# 04_ARM_B.net
KiCad netlist of a schematic drawn in Altium Designer
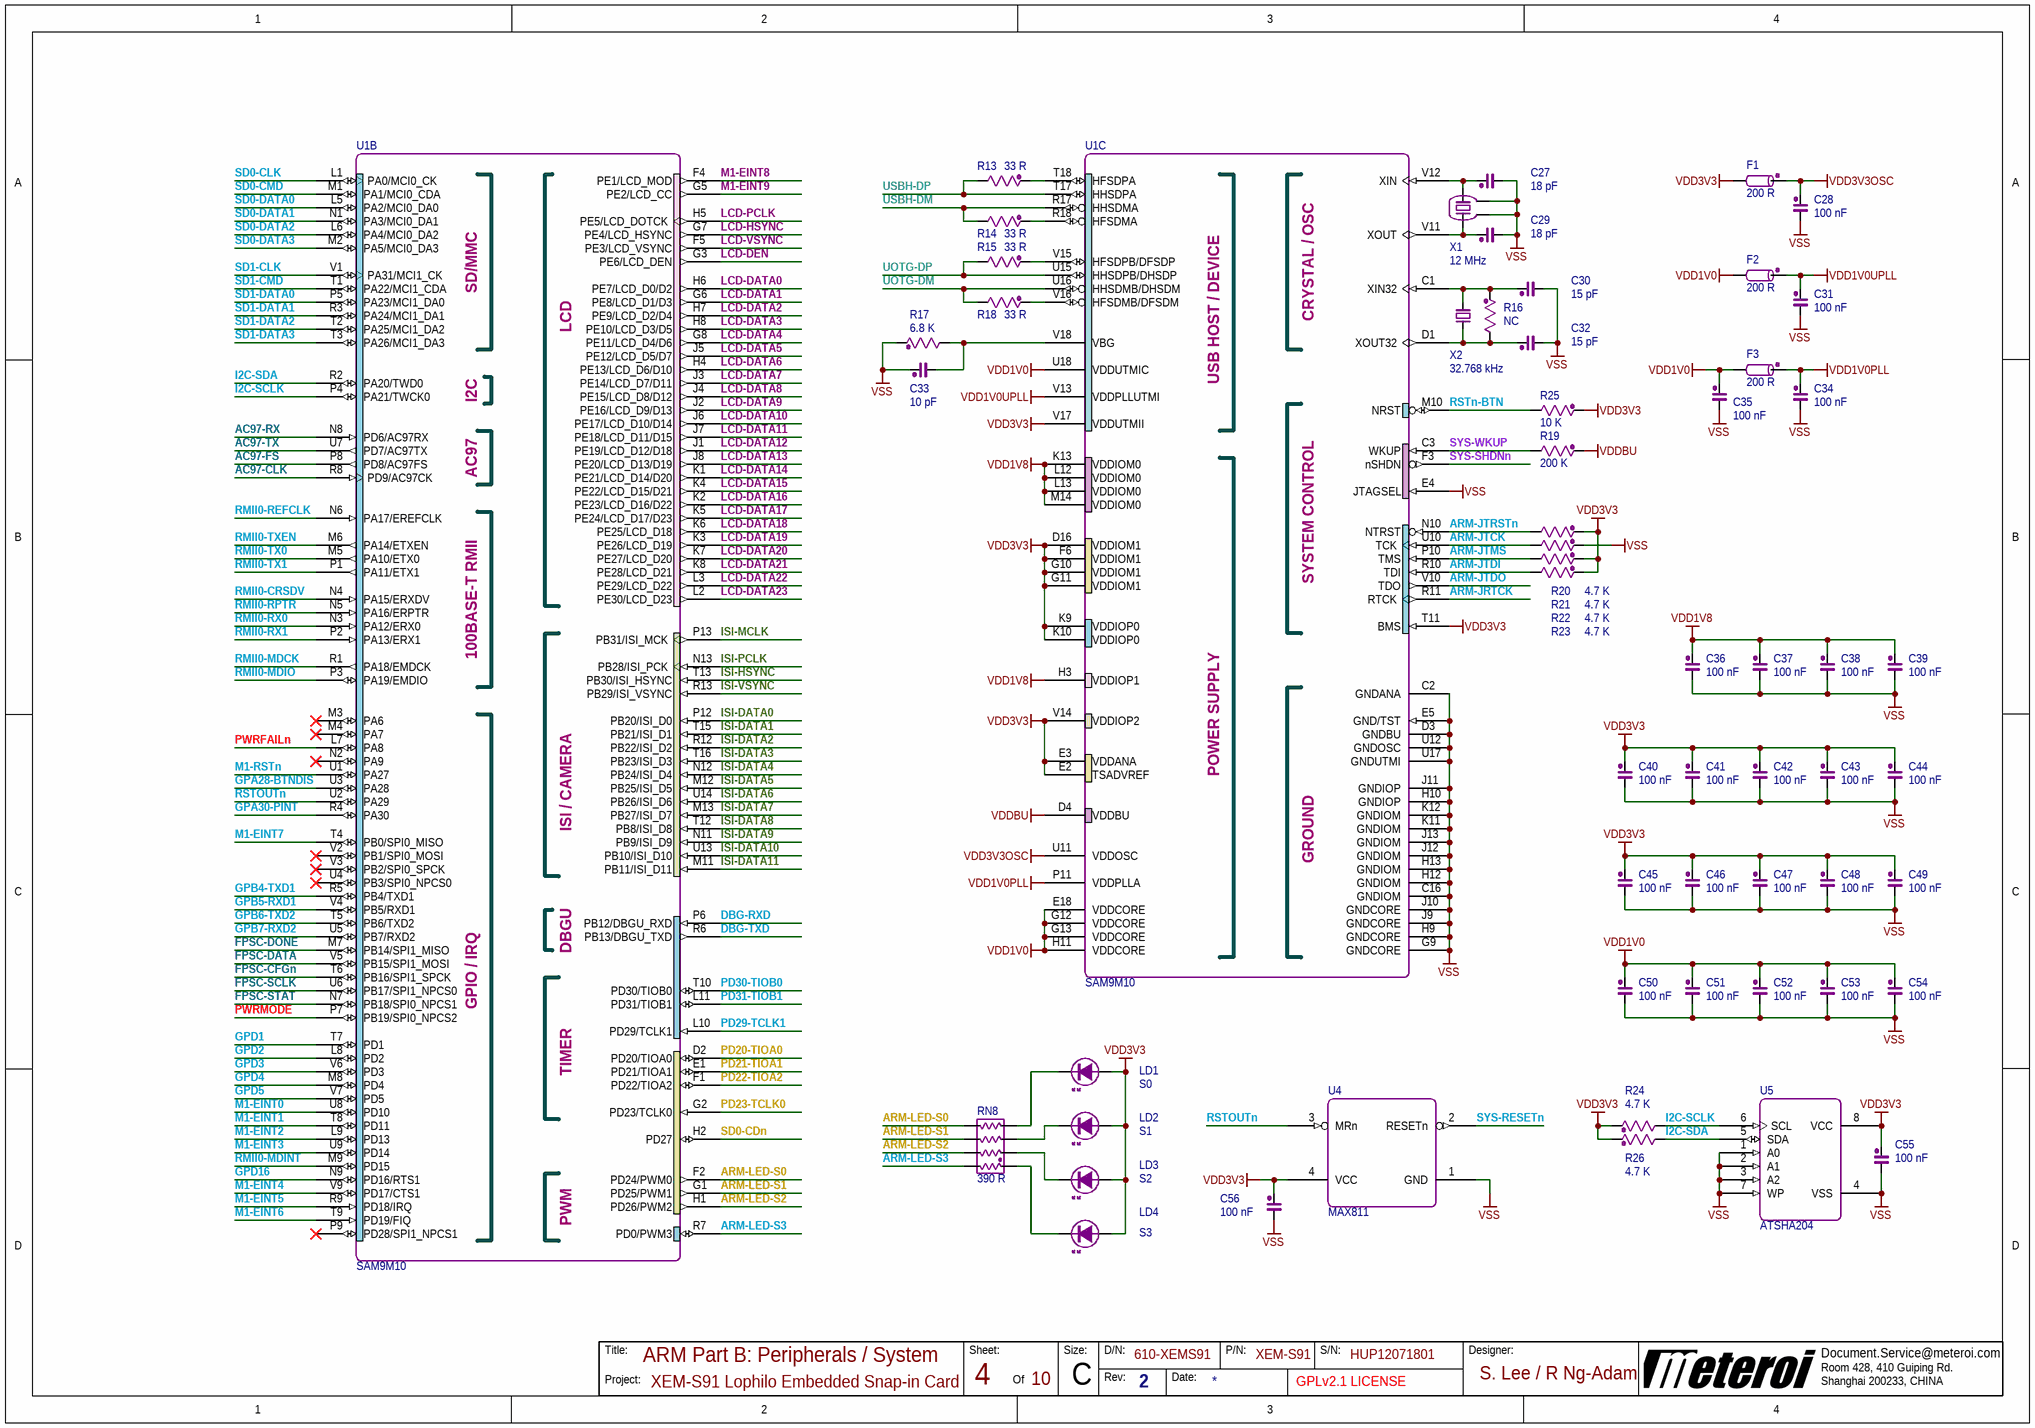
[diagram p0: 04_ARM_B.SchDoc]

(export (version "E")
  (design (tool "Eeschema 10.0.6"))
  (components
    (comp (ref "C27")
      (value "18 pF")
      (footprint "0402A1")
      (description "Normal Capacitor")
      (fields
        (field (name "PARTNUMBER") "0")
        (field (name "PUBLISHER") "Cowin")
        (field (name "DESIGNER") "shyul")
      )
      (libsource (lib "Basc_1_Passive") (part "CAP"))
    )
    (comp (ref "C28")
      (value "100 nF")
      (footprint "0402A1")
      (description "Normal Capacitor")
      (fields
        (field (name "PARTNUMBER") "0")
        (field (name "PUBLISHER") "Cowin")
        (field (name "DESIGNER") "shyul")
      )
      (libsource (lib "") (part "CAP_1"))
    )
    (comp (ref "C29")
      (value "18 pF")
      (footprint "0402A1")
      (description "Normal Capacitor")
      (fields
        (field (name "PARTNUMBER") "0")
        (field (name "PUBLISHER") "Cowin")
        (field (name "DESIGNER") "shyul")
      )
      (libsource (lib "Basc_1_Passive") (part "CAP"))
    )
    (comp (ref "C30")
      (value "15 pF")
      (footprint "0402A1")
      (description "Normal Capacitor")
      (fields
        (field (name "PARTNUMBER") "0")
        (field (name "PUBLISHER") "Cowin")
        (field (name "DESIGNER") "shyul")
      )
      (libsource (lib "Basc_1_Passive") (part "CAP"))
    )
    (comp (ref "C31")
      (value "100 nF")
      (footprint "0402A1")
      (description "Normal Capacitor")
      (fields
        (field (name "PARTNUMBER") "0")
        (field (name "PUBLISHER") "Cowin")
        (field (name "DESIGNER") "shyul")
      )
      (libsource (lib "") (part "CAP_1"))
    )
    (comp (ref "C32")
      (value "15 pF")
      (footprint "0402A1")
      (description "Normal Capacitor")
      (fields
        (field (name "PARTNUMBER") "0")
        (field (name "PUBLISHER") "Cowin")
        (field (name "DESIGNER") "shyul")
      )
      (libsource (lib "Basc_1_Passive") (part "CAP"))
    )
    (comp (ref "C33")
      (value "10 pF")
      (footprint "0402A1")
      (description "Normal Capacitor")
      (fields
        (field (name "PARTNUMBER") "0")
        (field (name "PUBLISHER") "Cowin")
        (field (name "DESIGNER") "shyul")
      )
      (libsource (lib "Basc_1_Passive") (part "CAP"))
    )
    (comp (ref "C34")
      (value "100 nF")
      (footprint "0402A1")
      (description "Normal Capacitor")
      (fields
        (field (name "PARTNUMBER") "0")
        (field (name "PUBLISHER") "Cowin")
        (field (name "DESIGNER") "shyul")
      )
      (libsource (lib "") (part "CAP_1"))
    )
    (comp (ref "C35")
      (value "100 nF")
      (footprint "0402A1")
      (description "Normal Capacitor")
      (fields
        (field (name "PARTNUMBER") "0")
        (field (name "PUBLISHER") "Cowin")
        (field (name "DESIGNER") "shyul")
      )
      (libsource (lib "") (part "CAP_1"))
    )
    (comp (ref "C36")
      (value "100 nF")
      (footprint "0402A1")
      (description "Normal Capacitor")
      (fields
        (field (name "PARTNUMBER") "0")
        (field (name "PUBLISHER") "Cowin")
        (field (name "DESIGNER") "shyul")
      )
      (libsource (lib "") (part "CAP_1"))
    )
    (comp (ref "C37")
      (value "100 nF")
      (footprint "0402A1")
      (description "Normal Capacitor")
      (fields
        (field (name "PARTNUMBER") "0")
        (field (name "PUBLISHER") "Cowin")
        (field (name "DESIGNER") "shyul")
      )
      (libsource (lib "") (part "CAP_1"))
    )
    (comp (ref "C38")
      (value "100 nF")
      (footprint "0402A1")
      (description "Normal Capacitor")
      (fields
        (field (name "PARTNUMBER") "0")
        (field (name "PUBLISHER") "Cowin")
        (field (name "DESIGNER") "shyul")
      )
      (libsource (lib "") (part "CAP_1"))
    )
    (comp (ref "C39")
      (value "100 nF")
      (footprint "0402A1")
      (description "Normal Capacitor")
      (fields
        (field (name "PARTNUMBER") "0")
        (field (name "PUBLISHER") "Cowin")
        (field (name "DESIGNER") "shyul")
      )
      (libsource (lib "") (part "CAP_1"))
    )
    (comp (ref "C40")
      (value "100 nF")
      (footprint "0402A1")
      (description "Normal Capacitor")
      (fields
        (field (name "PARTNUMBER") "0")
        (field (name "PUBLISHER") "Cowin")
        (field (name "DESIGNER") "shyul")
      )
      (libsource (lib "") (part "CAP_1"))
    )
    (comp (ref "C41")
      (value "100 nF")
      (footprint "0402A1")
      (description "Normal Capacitor")
      (fields
        (field (name "PARTNUMBER") "0")
        (field (name "PUBLISHER") "Cowin")
        (field (name "DESIGNER") "shyul")
      )
      (libsource (lib "") (part "CAP_1"))
    )
    (comp (ref "C42")
      (value "100 nF")
      (footprint "0402A1")
      (description "Normal Capacitor")
      (fields
        (field (name "PARTNUMBER") "0")
        (field (name "PUBLISHER") "Cowin")
        (field (name "DESIGNER") "shyul")
      )
      (libsource (lib "") (part "CAP_1"))
    )
    (comp (ref "C43")
      (value "100 nF")
      (footprint "0402A1")
      (description "Normal Capacitor")
      (fields
        (field (name "PARTNUMBER") "0")
        (field (name "PUBLISHER") "Cowin")
        (field (name "DESIGNER") "shyul")
      )
      (libsource (lib "") (part "CAP_1"))
    )
    (comp (ref "C44")
      (value "100 nF")
      (footprint "0402A1")
      (description "Normal Capacitor")
      (fields
        (field (name "PARTNUMBER") "0")
        (field (name "PUBLISHER") "Cowin")
        (field (name "DESIGNER") "shyul")
      )
      (libsource (lib "") (part "CAP_1"))
    )
    (comp (ref "C45")
      (value "100 nF")
      (footprint "0402A1")
      (description "Normal Capacitor")
      (fields
        (field (name "PARTNUMBER") "0")
        (field (name "PUBLISHER") "Cowin")
        (field (name "DESIGNER") "shyul")
      )
      (libsource (lib "") (part "CAP_1"))
    )
    (comp (ref "C46")
      (value "100 nF")
      (footprint "0402A1")
      (description "Normal Capacitor")
      (fields
        (field (name "PARTNUMBER") "0")
        (field (name "PUBLISHER") "Cowin")
        (field (name "DESIGNER") "shyul")
      )
      (libsource (lib "") (part "CAP_1"))
    )
    (comp (ref "C47")
      (value "100 nF")
      (footprint "0402A1")
      (description "Normal Capacitor")
      (fields
        (field (name "PARTNUMBER") "0")
        (field (name "PUBLISHER") "Cowin")
        (field (name "DESIGNER") "shyul")
      )
      (libsource (lib "") (part "CAP_1"))
    )
    (comp (ref "C48")
      (value "100 nF")
      (footprint "0402A1")
      (description "Normal Capacitor")
      (fields
        (field (name "PARTNUMBER") "0")
        (field (name "PUBLISHER") "Cowin")
        (field (name "DESIGNER") "shyul")
      )
      (libsource (lib "") (part "CAP_1"))
    )
    (comp (ref "C49")
      (value "100 nF")
      (footprint "0402A1")
      (description "Normal Capacitor")
      (fields
        (field (name "PARTNUMBER") "0")
        (field (name "PUBLISHER") "Cowin")
        (field (name "DESIGNER") "shyul")
      )
      (libsource (lib "") (part "CAP_1"))
    )
    (comp (ref "C50")
      (value "100 nF")
      (footprint "0402A1")
      (description "Normal Capacitor")
      (fields
        (field (name "PARTNUMBER") "0")
        (field (name "PUBLISHER") "Cowin")
        (field (name "DESIGNER") "shyul")
      )
      (libsource (lib "") (part "CAP_1"))
    )
    (comp (ref "C51")
      (value "100 nF")
      (footprint "0402A1")
      (description "Normal Capacitor")
      (fields
        (field (name "PARTNUMBER") "0")
        (field (name "PUBLISHER") "Cowin")
        (field (name "DESIGNER") "shyul")
      )
      (libsource (lib "") (part "CAP_1"))
    )
    (comp (ref "C52")
      (value "100 nF")
      (footprint "0402A1")
      (description "Normal Capacitor")
      (fields
        (field (name "PARTNUMBER") "0")
        (field (name "PUBLISHER") "Cowin")
        (field (name "DESIGNER") "shyul")
      )
      (libsource (lib "") (part "CAP_1"))
    )
    (comp (ref "C53")
      (value "100 nF")
      (footprint "0402A1")
      (description "Normal Capacitor")
      (fields
        (field (name "PARTNUMBER") "0")
        (field (name "PUBLISHER") "Cowin")
        (field (name "DESIGNER") "shyul")
      )
      (libsource (lib "") (part "CAP_1"))
    )
    (comp (ref "C54")
      (value "100 nF")
      (footprint "0402A1")
      (description "Normal Capacitor")
      (fields
        (field (name "PARTNUMBER") "0")
        (field (name "PUBLISHER") "Cowin")
        (field (name "DESIGNER") "shyul")
      )
      (libsource (lib "") (part "CAP_1"))
    )
    (comp (ref "C55")
      (value "100 nF")
      (footprint "0402A1")
      (description "Normal Capacitor")
      (fields
        (field (name "PARTNUMBER") "0")
        (field (name "PUBLISHER") "Cowin")
        (field (name "DESIGNER") "shyul")
      )
      (libsource (lib "") (part "CAP_1"))
    )
    (comp (ref "C56")
      (value "100 nF")
      (footprint "0402A1")
      (description "Normal Capacitor")
      (fields
        (field (name "PARTNUMBER") "0")
        (field (name "PUBLISHER") "Cowin")
        (field (name "DESIGNER") "shyul")
      )
      (libsource (lib "") (part "CAP_1"))
    )
    (comp (ref "F1")
      (value "200 R")
      (footprint "0402A3")
      (description "EMI Bead")
      (fields
        (field (name "PARTNUMBER") "BLM")
        (field (name "DESIGNER") "shyul")
        (field (name "PUBLISHER") "Cowin")
      )
      (libsource (lib "Basc_2_EMI_Protection") (part "BEAD"))
    )
    (comp (ref "F2")
      (value "200 R")
      (footprint "0402A3")
      (description "EMI Bead")
      (fields
        (field (name "PARTNUMBER") "BLM")
        (field (name "DESIGNER") "shyul")
        (field (name "PUBLISHER") "Cowin")
      )
      (libsource (lib "Basc_2_EMI_Protection") (part "BEAD"))
    )
    (comp (ref "F3")
      (value "200 R")
      (footprint "0402A3")
      (description "EMI Bead")
      (fields
        (field (name "PARTNUMBER") "BLM")
        (field (name "DESIGNER") "shyul")
        (field (name "PUBLISHER") "Cowin")
      )
      (libsource (lib "Basc_2_EMI_Protection") (part "BEAD"))
    )
    (comp (ref "LD1")
      (value "S0")
      (footprint "0603LD")
      (description "LED Single")
      (fields
        (field (name "PARTNUMBER") "0")
        (field (name "DESIGNER") "shyul")
        (field (name "PUBLISHER") "Cowin")
      )
      (libsource (lib "Basc_4_Other") (part "LED"))
    )
    (comp (ref "LD2")
      (value "S1")
      (footprint "0603LD")
      (description "LED Single")
      (fields
        (field (name "PARTNUMBER") "0")
        (field (name "DESIGNER") "shyul")
        (field (name "PUBLISHER") "Cowin")
      )
      (libsource (lib "Basc_4_Other") (part "LED"))
    )
    (comp (ref "LD3")
      (value "S2")
      (footprint "0603LD")
      (description "LED Single")
      (fields
        (field (name "PARTNUMBER") "0")
        (field (name "DESIGNER") "shyul")
        (field (name "PUBLISHER") "Cowin")
      )
      (libsource (lib "Basc_4_Other") (part "LED"))
    )
    (comp (ref "LD4")
      (value "S3")
      (footprint "0603LD")
      (description "LED Single")
      (fields
        (field (name "PARTNUMBER") "0")
        (field (name "DESIGNER") "shyul")
        (field (name "PUBLISHER") "Cowin")
      )
      (libsource (lib "Basc_4_Other") (part "LED"))
    )
    (comp (ref "R13")
      (value "33 R")
      (footprint "0402A2")
      (description "Normal Resistor")
      (fields
        (field (name "PARTNUMBER") "0")
        (field (name "DESIGNER") "shyul")
        (field (name "PUBLISHER") "Cowin")
      )
      (libsource (lib "Basc_1_Passive") (part "RES"))
    )
    (comp (ref "R14")
      (value "33 R")
      (footprint "0402A2")
      (description "Normal Resistor")
      (fields
        (field (name "PARTNUMBER") "0")
        (field (name "DESIGNER") "shyul")
        (field (name "PUBLISHER") "Cowin")
      )
      (libsource (lib "Basc_1_Passive") (part "RES"))
    )
    (comp (ref "R15")
      (value "33 R")
      (footprint "0402A2")
      (description "Normal Resistor")
      (fields
        (field (name "PARTNUMBER") "0")
        (field (name "DESIGNER") "shyul")
        (field (name "PUBLISHER") "Cowin")
      )
      (libsource (lib "Basc_1_Passive") (part "RES"))
    )
    (comp (ref "R16")
      (value "NC")
      (footprint "0402A2")
      (description "Normal Resistor")
      (fields
        (field (name "PARTNUMBER") "0")
        (field (name "DESIGNER") "shyul")
        (field (name "PUBLISHER") "Cowin")
      )
      (libsource (lib "Basc_1_Passive") (part "RES"))
    )
    (comp (ref "R17")
      (value "6.8 K")
      (footprint "0402A2")
      (description "Normal Resistor")
      (fields
        (field (name "PARTNUMBER") "0")
        (field (name "DESIGNER") "shyul")
        (field (name "PUBLISHER") "Cowin")
      )
      (libsource (lib "Basc_1_Passive") (part "RES"))
    )
    (comp (ref "R18")
      (value "33 R")
      (footprint "0402A2")
      (description "Normal Resistor")
      (fields
        (field (name "PARTNUMBER") "0")
        (field (name "DESIGNER") "shyul")
        (field (name "PUBLISHER") "Cowin")
      )
      (libsource (lib "Basc_1_Passive") (part "RES"))
    )
    (comp (ref "R19")
      (value "200 K")
      (footprint "0402A2")
      (description "Normal Resistor")
      (fields
        (field (name "PARTNUMBER") "0")
        (field (name "DESIGNER") "shyul")
        (field (name "PUBLISHER") "Cowin")
      )
      (libsource (lib "Basc_1_Passive") (part "RES"))
    )
    (comp (ref "R20")
      (value "4.7 K")
      (footprint "0402A2")
      (description "Normal Resistor")
      (fields
        (field (name "PARTNUMBER") "0")
        (field (name "DESIGNER") "shyul")
        (field (name "PUBLISHER") "Cowin")
      )
      (libsource (lib "Basc_1_Passive") (part "RES"))
    )
    (comp (ref "R21")
      (value "4.7 K")
      (footprint "0402A2")
      (description "Normal Resistor")
      (fields
        (field (name "PARTNUMBER") "0")
        (field (name "DESIGNER") "shyul")
        (field (name "PUBLISHER") "Cowin")
      )
      (libsource (lib "Basc_1_Passive") (part "RES"))
    )
    (comp (ref "R22")
      (value "4.7 K")
      (footprint "0402A2")
      (description "Normal Resistor")
      (fields
        (field (name "PARTNUMBER") "0")
        (field (name "DESIGNER") "shyul")
        (field (name "PUBLISHER") "Cowin")
      )
      (libsource (lib "Basc_1_Passive") (part "RES"))
    )
    (comp (ref "R23")
      (value "4.7 K")
      (footprint "0402A2")
      (description "Normal Resistor")
      (fields
        (field (name "PARTNUMBER") "0")
        (field (name "DESIGNER") "shyul")
        (field (name "PUBLISHER") "Cowin")
      )
      (libsource (lib "Basc_1_Passive") (part "RES"))
    )
    (comp (ref "R24")
      (value "4.7 K")
      (footprint "0402A2")
      (description "Normal Resistor")
      (fields
        (field (name "PARTNUMBER") "0")
        (field (name "DESIGNER") "shyul")
        (field (name "PUBLISHER") "Cowin")
      )
      (libsource (lib "Basc_1_Passive") (part "RES"))
    )
    (comp (ref "R25")
      (value "10 K")
      (footprint "0402A2")
      (description "Normal Resistor")
      (fields
        (field (name "PARTNUMBER") "0")
        (field (name "DESIGNER") "shyul")
        (field (name "PUBLISHER") "Cowin")
      )
      (libsource (lib "Basc_1_Passive") (part "RES"))
    )
    (comp (ref "R26")
      (value "4.7 K")
      (footprint "0402A2")
      (description "Normal Resistor")
      (fields
        (field (name "PARTNUMBER") "0")
        (field (name "DESIGNER") "shyul")
        (field (name "PUBLISHER") "Cowin")
      )
      (libsource (lib "Basc_1_Passive") (part "RES"))
    )
    (comp (ref "RN8")
      (value "390 R")
      (footprint "0402PR4")
      (description "Resistor Array x4")
      (fields
        (field (name "PARTNUMBER") "YC124-JR-07390RL")
        (field (name "PUBLISHER") "Cowin")
        (field (name "DESIGNER") "shyul")
      )
      (libsource (lib "Basc_1_Passive") (part "RES_N4"))
    )
    (comp (ref "U1")
      (value "SAM9M10")
      (footprint "TFBGA-324")
      (description "SAM9M10 Embedded Processor")
      (fields
        (field (name "PARTNUMBER") "AT91SAM9M10-CU")
        (field (name "DESIGNER") "shyul")
        (field (name "PUBLISHER") "Cowin")
      )
      (libsource (lib "PCB_XEM-S91") (part "SAM9M10"))
    )
    (comp (ref "U4")
      (value "MAX811")
      (footprint "SOT-143")
      (description "Generic nReset")
      (fields
        (field (name "PARTNUMBER") "MAX811SEUS-T")
        (field (name "PUBLISHER") "Cowin")
        (field (name "DESIGNER") "shyul")
      )
      (libsource (lib "IC_03_MCU") (part "MAX811"))
    )
    (comp (ref "U5")
      (value "ATSHA204")
      (footprint "SOIC-8S")
      (description "Generic 24 Series I2C ROM")
      (fields
        (field (name "PARTNUMBER") "ATSHA204-SH-DA")
        (field (name "PUBLISHER") "Cowin")
        (field (name "DESIGNER") "shyul")
      )
      (libsource (lib "IC_03_MCU") (part "ROM_I2C_A"))
    )
    (comp (ref "X1")
      (value "12 MHz")
      (footprint "OSC_4A_S_3225")
      (description "Crystal")
      (fields
        (field (name "PARTNUMBER") "0")
        (field (name "PUBLISHER") "Cowin")
        (field (name "DESIGNER") "shyul")
      )
      (libsource (lib "Basc_4_Other") (part "OSC_2B"))
    )
    (comp (ref "X2")
      (value "32.768 kHz")
      (footprint "OSC_2A_S_4918")
      (description "Crystal")
      (fields
        (field (name "PARTNUMBER") "0")
        (field (name "PUBLISHER") "Cowin")
        (field (name "DESIGNER") "shyul")
      )
      (libsource (lib "Basc_4_Other") (part "OSC_2A"))
    )
  )
  (nets
    (net (code "1") (name "/AC97-CLK") (class "Default")
      (node (ref "U1") (pin "R8") (pinfunction "PD9/AC97CK_R8") (pintype "input"))
    )
    (net (code "2") (name "/AC97-FS") (class "Default")
      (node (ref "U1") (pin "P8") (pinfunction "PD8/AC97FS_P8") (pintype "output"))
    )
    (net (code "3") (name "/AC97-RX") (class "Default")
      (node (ref "U1") (pin "N8") (pinfunction "PD6/AC97RX_N8") (pintype "input"))
    )
    (net (code "4") (name "/AC97-TX") (class "Default")
      (node (ref "U1") (pin "U7") (pinfunction "PD7/AC97TX_U7") (pintype "output"))
    )
    (net (code "5") (name "/ARM-JRTCK") (class "Default")
      (node (ref "U1") (pin "R11") (pinfunction "RTCK_R11") (pintype "output"))
    )
    (net (code "6") (name "/ARM-JTCK") (class "Default")
      (node (ref "R21") (pin "1") (pinfunction "1_1") (pintype "passive"))
      (node (ref "U1") (pin "U10") (pinfunction "TCK_U10") (pintype "input"))
    )
    (net (code "7") (name "/ARM-JTDI") (class "Default")
      (node (ref "R23") (pin "1") (pinfunction "1_1") (pintype "passive"))
      (node (ref "U1") (pin "R10") (pinfunction "TDI_R10") (pintype "input"))
    )
    (net (code "8") (name "/ARM-JTDO") (class "Default")
      (node (ref "U1") (pin "V10") (pinfunction "TDO_V10") (pintype "output"))
    )
    (net (code "9") (name "/ARM-JTMS") (class "Default")
      (node (ref "R22") (pin "1") (pinfunction "1_1") (pintype "passive"))
      (node (ref "U1") (pin "P10") (pinfunction "TMS_P10") (pintype "input"))
    )
    (net (code "10") (name "/ARM-JTRSTn") (class "Default")
      (node (ref "R20") (pin "1") (pinfunction "1_1") (pintype "passive"))
      (node (ref "U1") (pin "N10") (pinfunction "NTRST_N10") (pintype "input"))
    )
    (net (code "11") (name "/ARM-LED-S0") (class "Default")
      (node (ref "RN8") (pin "8") (pinfunction "8_8") (pintype "passive"))
      (node (ref "U1") (pin "F2") (pinfunction "PD24/PWM0_F2") (pintype "output"))
    )
    (net (code "12") (name "/ARM-LED-S1") (class "Default")
      (node (ref "RN8") (pin "6") (pinfunction "6_6") (pintype "passive"))
      (node (ref "U1") (pin "G1") (pinfunction "PD25/PWM1_G1") (pintype "output"))
    )
    (net (code "13") (name "/ARM-LED-S2") (class "Default")
      (node (ref "RN8") (pin "4") (pinfunction "4_4") (pintype "passive"))
      (node (ref "U1") (pin "H1") (pinfunction "PD26/PWM2_H1") (pintype "output"))
    )
    (net (code "14") (name "/ARM-LED-S3") (class "Default")
      (node (ref "RN8") (pin "2") (pinfunction "2_2") (pintype "passive"))
      (node (ref "U1") (pin "R7") (pinfunction "PD0/PWM3_R7") (pintype "bidirectional"))
    )
    (net (code "15") (name "/DBG-RXD") (class "Default")
      (node (ref "U1") (pin "P6") (pinfunction "PB12/DBGU_RXD_P6") (pintype "input"))
    )
    (net (code "16") (name "/DBG-TXD") (class "Default")
      (node (ref "U1") (pin "R6") (pinfunction "PB13/DBGU_TXD_R6") (pintype "output"))
    )
    (net (code "17") (name "/FPSC-CFGn") (class "Default")
      (node (ref "U1") (pin "T6") (pinfunction "PB16/SPI1_SPCK_T6") (pintype "bidirectional"))
    )
    (net (code "18") (name "/FPSC-DATA") (class "Default")
      (node (ref "U1") (pin "V5") (pinfunction "PB15/SPI1_MOSI_V5") (pintype "bidirectional"))
    )
    (net (code "19") (name "/FPSC-DONE") (class "Default")
      (node (ref "U1") (pin "M7") (pinfunction "PB14/SPI1_MISO_M7") (pintype "bidirectional"))
    )
    (net (code "20") (name "/FPSC-SCLK") (class "Default")
      (node (ref "U1") (pin "U6") (pinfunction "PB17/SPI1_NPCS0_U6") (pintype "bidirectional"))
    )
    (net (code "21") (name "/FPSC-STAT") (class "Default")
      (node (ref "U1") (pin "N7") (pinfunction "PB18/SPI0_NPCS1_N7") (pintype "bidirectional"))
    )
    (net (code "22") (name "/GPA28-BTNDIS") (class "Default")
      (node (ref "U1") (pin "U3") (pinfunction "PA28_U3") (pintype "bidirectional"))
    )
    (net (code "23") (name "/GPA30-PINT") (class "Default")
      (node (ref "U1") (pin "R4") (pinfunction "PA30_R4") (pintype "bidirectional"))
    )
    (net (code "24") (name "/GPB4-TXD1") (class "Default")
      (node (ref "U1") (pin "R5") (pinfunction "PB4/TXD1_R5") (pintype "bidirectional"))
    )
    (net (code "25") (name "/GPB5-RXD1") (class "Default")
      (node (ref "U1") (pin "V4") (pinfunction "PB5/RXD1_V4") (pintype "bidirectional"))
    )
    (net (code "26") (name "/GPB6-TXD2") (class "Default")
      (node (ref "U1") (pin "T5") (pinfunction "PB6/TXD2_T5") (pintype "bidirectional"))
    )
    (net (code "27") (name "/GPB7-RXD2") (class "Default")
      (node (ref "U1") (pin "U5") (pinfunction "PB7/RXD2_U5") (pintype "bidirectional"))
    )
    (net (code "28") (name "/GPD1") (class "Default")
      (node (ref "U1") (pin "T7") (pinfunction "PD1_T7") (pintype "bidirectional"))
    )
    (net (code "29") (name "/GPD2") (class "Default")
      (node (ref "U1") (pin "L8") (pinfunction "PD2_L8") (pintype "bidirectional"))
    )
    (net (code "30") (name "/GPD3") (class "Default")
      (node (ref "U1") (pin "V6") (pinfunction "PD3_V6") (pintype "bidirectional"))
    )
    (net (code "31") (name "/GPD4") (class "Default")
      (node (ref "U1") (pin "M8") (pinfunction "PD4_M8") (pintype "bidirectional"))
    )
    (net (code "32") (name "/GPD5") (class "Default")
      (node (ref "U1") (pin "V7") (pinfunction "PD5_V7") (pintype "bidirectional"))
    )
    (net (code "33") (name "/GPD16") (class "Default")
      (node (ref "U1") (pin "N9") (pinfunction "PD16/RTS1_N9") (pintype "bidirectional"))
    )
    (net (code "34") (name "/I2C-SCLK") (class "Default")
      (node (ref "R24") (pin "1") (pinfunction "1_1") (pintype "passive"))
      (node (ref "U1") (pin "P4") (pinfunction "PA21/TWCK0_P4") (pintype "bidirectional"))
      (node (ref "U5") (pin "6") (pinfunction "SCL_6") (pintype "input"))
    )
    (net (code "35") (name "/I2C-SDA") (class "Default")
      (node (ref "R26") (pin "1") (pinfunction "1_1") (pintype "passive"))
      (node (ref "U1") (pin "R2") (pinfunction "PA20/TWD0_R2") (pintype "bidirectional"))
      (node (ref "U5") (pin "5") (pinfunction "SDA_5") (pintype "bidirectional"))
    )
    (net (code "36") (name "/ISI-DATA0") (class "Default")
      (node (ref "U1") (pin "P12") (pinfunction "PB20/ISI_D0_P12") (pintype "input"))
    )
    (net (code "37") (name "/ISI-DATA1") (class "Default")
      (node (ref "U1") (pin "T15") (pinfunction "PB21/ISI_D1_T15") (pintype "input"))
    )
    (net (code "38") (name "/ISI-DATA2") (class "Default")
      (node (ref "U1") (pin "R12") (pinfunction "PB22/ISI_D2_R12") (pintype "input"))
    )
    (net (code "39") (name "/ISI-DATA3") (class "Default")
      (node (ref "U1") (pin "T16") (pinfunction "PB23/ISI_D3_T16") (pintype "input"))
    )
    (net (code "40") (name "/ISI-DATA4") (class "Default")
      (node (ref "U1") (pin "N12") (pinfunction "PB24/ISI_D4_N12") (pintype "input"))
    )
    (net (code "41") (name "/ISI-DATA5") (class "Default")
      (node (ref "U1") (pin "M12") (pinfunction "PB25/ISI_D5_M12") (pintype "input"))
    )
    (net (code "42") (name "/ISI-DATA6") (class "Default")
      (node (ref "U1") (pin "U14") (pinfunction "PB26/ISI_D6_U14") (pintype "input"))
    )
    (net (code "43") (name "/ISI-DATA7") (class "Default")
      (node (ref "U1") (pin "M13") (pinfunction "PB27/ISI_D7_M13") (pintype "input"))
    )
    (net (code "44") (name "/ISI-DATA8") (class "Default")
      (node (ref "U1") (pin "T12") (pinfunction "PB8/ISI_D8_T12") (pintype "input"))
    )
    (net (code "45") (name "/ISI-DATA9") (class "Default")
      (node (ref "U1") (pin "N11") (pinfunction "PB9/ISI_D9_N11") (pintype "input"))
    )
    (net (code "46") (name "/ISI-DATA10") (class "Default")
      (node (ref "U1") (pin "U13") (pinfunction "PB10/ISI_D10_U13") (pintype "input"))
    )
    (net (code "47") (name "/ISI-DATA11") (class "Default")
      (node (ref "U1") (pin "M11") (pinfunction "PB11/ISI_D11_M11") (pintype "input"))
    )
    (net (code "48") (name "/ISI-HSYNC") (class "Default")
      (node (ref "U1") (pin "T13") (pinfunction "PB30/ISI_HSYNC_T13") (pintype "input"))
    )
    (net (code "49") (name "/ISI-MCLK") (class "Default")
      (node (ref "U1") (pin "P13") (pinfunction "PB31/ISI_MCK_P13") (pintype "output"))
    )
    (net (code "50") (name "/ISI-PCLK") (class "Default")
      (node (ref "U1") (pin "N13") (pinfunction "PB28/ISI_PCK_N13") (pintype "input"))
    )
    (net (code "51") (name "/ISI-VSYNC") (class "Default")
      (node (ref "U1") (pin "R13") (pinfunction "PB29/ISI_VSYNC_R13") (pintype "input"))
    )
    (net (code "52") (name "/LCD-DATA0") (class "Default")
      (node (ref "U1") (pin "H6") (pinfunction "PE7/LCD_D0/D2_H6") (pintype "output"))
    )
    (net (code "53") (name "/LCD-DATA1") (class "Default")
      (node (ref "U1") (pin "G6") (pinfunction "PE8/LCD_D1/D3_G6") (pintype "output"))
    )
    (net (code "54") (name "/LCD-DATA2") (class "Default")
      (node (ref "U1") (pin "H7") (pinfunction "PE9/LCD_D2/D4_H7") (pintype "output"))
    )
    (net (code "55") (name "/LCD-DATA3") (class "Default")
      (node (ref "U1") (pin "H8") (pinfunction "PE10/LCD_D3/D5_H8") (pintype "output"))
    )
    (net (code "56") (name "/LCD-DATA4") (class "Default")
      (node (ref "U1") (pin "G8") (pinfunction "PE11/LCD_D4/D6_G8") (pintype "output"))
    )
    (net (code "57") (name "/LCD-DATA5") (class "Default")
      (node (ref "U1") (pin "J5") (pinfunction "PE12/LCD_D5/D7_J5") (pintype "output"))
    )
    (net (code "58") (name "/LCD-DATA6") (class "Default")
      (node (ref "U1") (pin "H4") (pinfunction "PE13/LCD_D6/D10_H4") (pintype "output"))
    )
    (net (code "59") (name "/LCD-DATA7") (class "Default")
      (node (ref "U1") (pin "J3") (pinfunction "PE14/LCD_D7/D11_J3") (pintype "output"))
    )
    (net (code "60") (name "/LCD-DATA8") (class "Default")
      (node (ref "U1") (pin "J4") (pinfunction "PE15/LCD_D8/D12_J4") (pintype "output"))
    )
    (net (code "61") (name "/LCD-DATA9") (class "Default")
      (node (ref "U1") (pin "J2") (pinfunction "PE16/LCD_D9/D13_J2") (pintype "output"))
    )
    (net (code "62") (name "/LCD-DATA10") (class "Default")
      (node (ref "U1") (pin "J6") (pinfunction "PE17/LCD_D10/D14_J6") (pintype "output"))
    )
    (net (code "63") (name "/LCD-DATA11") (class "Default")
      (node (ref "U1") (pin "J7") (pinfunction "PE18/LCD_D11/D15_J7") (pintype "output"))
    )
    (net (code "64") (name "/LCD-DATA12") (class "Default")
      (node (ref "U1") (pin "J1") (pinfunction "PE19/LCD_D12/D18_J1") (pintype "output"))
    )
    (net (code "65") (name "/LCD-DATA13") (class "Default")
      (node (ref "U1") (pin "J8") (pinfunction "PE20/LCD_D13/D19_J8") (pintype "output"))
    )
    (net (code "66") (name "/LCD-DATA14") (class "Default")
      (node (ref "U1") (pin "K1") (pinfunction "PE21/LCD_D14/D20_K1") (pintype "output"))
    )
    (net (code "67") (name "/LCD-DATA15") (class "Default")
      (node (ref "U1") (pin "K4") (pinfunction "PE22/LCD_D15/D21_K4") (pintype "output"))
    )
    (net (code "68") (name "/LCD-DATA16") (class "Default")
      (node (ref "U1") (pin "K2") (pinfunction "PE23/LCD_D16/D22_K2") (pintype "output"))
    )
    (net (code "69") (name "/LCD-DATA17") (class "Default")
      (node (ref "U1") (pin "K5") (pinfunction "PE24/LCD_D17/D23_K5") (pintype "output"))
    )
    (net (code "70") (name "/LCD-DATA18") (class "Default")
      (node (ref "U1") (pin "K6") (pinfunction "PE25/LCD_D18_K6") (pintype "output"))
    )
    (net (code "71") (name "/LCD-DATA19") (class "Default")
      (node (ref "U1") (pin "K3") (pinfunction "PE26/LCD_D19_K3") (pintype "output"))
    )
    (net (code "72") (name "/LCD-DATA20") (class "Default")
      (node (ref "U1") (pin "K7") (pinfunction "PE27/LCD_D20_K7") (pintype "output"))
    )
    (net (code "73") (name "/LCD-DATA21") (class "Default")
      (node (ref "U1") (pin "K8") (pinfunction "PE28/LCD_D21_K8") (pintype "output"))
    )
    (net (code "74") (name "/LCD-DATA22") (class "Default")
      (node (ref "U1") (pin "L3") (pinfunction "PE29/LCD_D22_L3") (pintype "output"))
    )
    (net (code "75") (name "/LCD-DATA23") (class "Default")
      (node (ref "U1") (pin "L2") (pinfunction "PE30/LCD_D23_L2") (pintype "output"))
    )
    (net (code "76") (name "/LCD-DEN") (class "Default")
      (node (ref "U1") (pin "G3") (pinfunction "PE6/LCD_DEN_G3") (pintype "output"))
    )
    (net (code "77") (name "/LCD-HSYNC") (class "Default")
      (node (ref "U1") (pin "G7") (pinfunction "PE4/LCD_HSYNC_G7") (pintype "output"))
    )
    (net (code "78") (name "/LCD-PCLK") (class "Default")
      (node (ref "U1") (pin "H5") (pinfunction "PE5/LCD_DOTCK_H5") (pintype "output"))
    )
    (net (code "79") (name "/LCD-VSYNC") (class "Default")
      (node (ref "U1") (pin "F5") (pinfunction "PE3/LCD_VSYNC_F5") (pintype "output"))
    )
    (net (code "80") (name "/M1-EINT0") (class "Default")
      (node (ref "U1") (pin "U8") (pinfunction "PD10_U8") (pintype "bidirectional"))
    )
    (net (code "81") (name "/M1-EINT1") (class "Default")
      (node (ref "U1") (pin "T8") (pinfunction "PD11_T8") (pintype "bidirectional"))
    )
    (net (code "82") (name "/M1-EINT2") (class "Default")
      (node (ref "U1") (pin "L9") (pinfunction "PD13_L9") (pintype "bidirectional"))
    )
    (net (code "83") (name "/M1-EINT3") (class "Default")
      (node (ref "U1") (pin "U9") (pinfunction "PD14_U9") (pintype "bidirectional"))
    )
    (net (code "84") (name "/M1-EINT4") (class "Default")
      (node (ref "U1") (pin "V9") (pinfunction "PD17/CTS1_V9") (pintype "bidirectional"))
    )
    (net (code "85") (name "/M1-EINT5") (class "Default")
      (node (ref "U1") (pin "R9") (pinfunction "PD18/IRQ_R9") (pintype "input"))
    )
    (net (code "86") (name "/M1-EINT6") (class "Default")
      (node (ref "U1") (pin "T9") (pinfunction "PD19/FIQ_T9") (pintype "input"))
    )
    (net (code "87") (name "/M1-EINT7") (class "Default")
      (node (ref "U1") (pin "T4") (pinfunction "PB0/SPI0_MISO_T4") (pintype "bidirectional"))
    )
    (net (code "88") (name "/M1-EINT8") (class "Default")
      (node (ref "U1") (pin "F4") (pinfunction "PE1/LCD_MOD_F4") (pintype "output"))
    )
    (net (code "89") (name "/M1-EINT9") (class "Default")
      (node (ref "U1") (pin "G5") (pinfunction "PE2/LCD_CC_G5") (pintype "output"))
    )
    (net (code "90") (name "/M1-RSTn") (class "Default")
      (node (ref "U1") (pin "U1") (pinfunction "PA27_U1") (pintype "bidirectional"))
    )
    (net (code "91") (name "/PD20-TIOA0") (class "Default")
      (node (ref "U1") (pin "D2") (pinfunction "PD20/TIOA0_D2") (pintype "bidirectional"))
    )
    (net (code "92") (name "/PD21-TIOA1") (class "Default")
      (node (ref "U1") (pin "E1") (pinfunction "PD21/TIOA1_E1") (pintype "bidirectional"))
    )
    (net (code "93") (name "/PD22-TIOA2") (class "Default")
      (node (ref "U1") (pin "F1") (pinfunction "PD22/TIOA2_F1") (pintype "bidirectional"))
    )
    (net (code "94") (name "/PD23-TCLK0") (class "Default")
      (node (ref "U1") (pin "G2") (pinfunction "PD23/TCLK0_G2") (pintype "input"))
    )
    (net (code "95") (name "/PD29-TCLK1") (class "Default")
      (node (ref "U1") (pin "L10") (pinfunction "PD29/TCLK1_L10") (pintype "input"))
    )
    (net (code "96") (name "/PD30-TIOB0") (class "Default")
      (node (ref "U1") (pin "T10") (pinfunction "PD30/TIOB0_T10") (pintype "bidirectional"))
    )
    (net (code "97") (name "/PD31-TIOB1") (class "Default")
      (node (ref "U1") (pin "L11") (pinfunction "PD31/TIOB1_L11") (pintype "bidirectional"))
    )
    (net (code "98") (name "/PWRFAILn") (class "Default")
      (node (ref "U1") (pin "L7") (pinfunction "PA8_L7") (pintype "bidirectional"))
    )
    (net (code "99") (name "/PWRMODE") (class "Default")
      (node (ref "U1") (pin "P7") (pinfunction "PB19/SPI0_NPCS2_P7") (pintype "bidirectional"))
    )
    (net (code "100") (name "/RMII0-CRSDV") (class "Default")
      (node (ref "U1") (pin "N4") (pinfunction "PA15/ERXDV_N4") (pintype "input"))
    )
    (net (code "101") (name "/RMII0-MDCK") (class "Default")
      (node (ref "U1") (pin "R1") (pinfunction "PA18/EMDCK_R1") (pintype "output"))
    )
    (net (code "102") (name "/RMII0-MDINT") (class "Default")
      (node (ref "U1") (pin "M9") (pinfunction "PD15_M9") (pintype "bidirectional"))
    )
    (net (code "103") (name "/RMII0-MDIO") (class "Default")
      (node (ref "U1") (pin "P3") (pinfunction "PA19/EMDIO_P3") (pintype "bidirectional"))
    )
    (net (code "104") (name "/RMII0-REFCLK") (class "Default")
      (node (ref "U1") (pin "N6") (pinfunction "PA17/EREFCLK_N6") (pintype "input"))
    )
    (net (code "105") (name "/RMII0-RPTR") (class "Default")
      (node (ref "U1") (pin "N5") (pinfunction "PA16/ERPTR_N5") (pintype "input"))
    )
    (net (code "106") (name "/RMII0-RX0") (class "Default")
      (node (ref "U1") (pin "N3") (pinfunction "PA12/ERX0_N3") (pintype "input"))
    )
    (net (code "107") (name "/RMII0-RX1") (class "Default")
      (node (ref "U1") (pin "P2") (pinfunction "PA13/ERX1_P2") (pintype "input"))
    )
    (net (code "108") (name "/RMII0-TX0") (class "Default")
      (node (ref "U1") (pin "M5") (pinfunction "PA10/ETX0_M5") (pintype "output"))
    )
    (net (code "109") (name "/RMII0-TX1") (class "Default")
      (node (ref "U1") (pin "P1") (pinfunction "PA11/ETX1_P1") (pintype "output"))
    )
    (net (code "110") (name "/RMII0-TXEN") (class "Default")
      (node (ref "U1") (pin "M6") (pinfunction "PA14/ETXEN_M6") (pintype "output"))
    )
    (net (code "111") (name "/RSTOUTn") (class "Default")
      (node (ref "U1") (pin "U2") (pinfunction "PA29_U2") (pintype "bidirectional"))
      (node (ref "U4") (pin "3") (pinfunction "MRn_3") (pintype "input"))
    )
    (net (code "112") (name "/RSTn-BTN") (class "Default")
      (node (ref "R25") (pin "1") (pinfunction "1_1") (pintype "passive"))
      (node (ref "U1") (pin "M10") (pinfunction "NRST_M10") (pintype "bidirectional"))
    )
    (net (code "113") (name "/SD0-CDn") (class "Default")
      (node (ref "U1") (pin "H2") (pinfunction "PD27_H2") (pintype "bidirectional"))
    )
    (net (code "114") (name "/SD0-CLK") (class "Default")
      (node (ref "U1") (pin "L1") (pinfunction "PA0/MCI0_CK_L1") (pintype "bidirectional"))
    )
    (net (code "115") (name "/SD0-CMD") (class "Default")
      (node (ref "U1") (pin "M1") (pinfunction "PA1/MCI0_CDA_M1") (pintype "bidirectional"))
    )
    (net (code "116") (name "/SD0-DATA0") (class "Default")
      (node (ref "U1") (pin "L5") (pinfunction "PA2/MCI0_DA0_L5") (pintype "bidirectional"))
    )
    (net (code "117") (name "/SD0-DATA1") (class "Default")
      (node (ref "U1") (pin "N1") (pinfunction "PA3/MCI0_DA1_N1") (pintype "bidirectional"))
    )
    (net (code "118") (name "/SD0-DATA2") (class "Default")
      (node (ref "U1") (pin "L6") (pinfunction "PA4/MCI0_DA2_L6") (pintype "bidirectional"))
    )
    (net (code "119") (name "/SD0-DATA3") (class "Default")
      (node (ref "U1") (pin "M2") (pinfunction "PA5/MCI0_DA3_M2") (pintype "bidirectional"))
    )
    (net (code "120") (name "/SD1-CLK") (class "Default")
      (node (ref "U1") (pin "V1") (pinfunction "PA31/MCI1_CK_V1") (pintype "bidirectional"))
    )
    (net (code "121") (name "/SD1-CMD") (class "Default")
      (node (ref "U1") (pin "T1") (pinfunction "PA22/MCI1_CDA_T1") (pintype "bidirectional"))
    )
    (net (code "122") (name "/SD1-DATA0") (class "Default")
      (node (ref "U1") (pin "P5") (pinfunction "PA23/MCI1_DA0_P5") (pintype "bidirectional"))
    )
    (net (code "123") (name "/SD1-DATA1") (class "Default")
      (node (ref "U1") (pin "R3") (pinfunction "PA24/MCI1_DA1_R3") (pintype "bidirectional"))
    )
    (net (code "124") (name "/SD1-DATA2") (class "Default")
      (node (ref "U1") (pin "T2") (pinfunction "PA25/MCI1_DA2_T2") (pintype "bidirectional"))
    )
    (net (code "125") (name "/SD1-DATA3") (class "Default")
      (node (ref "U1") (pin "T3") (pinfunction "PA26/MCI1_DA3_T3") (pintype "bidirectional"))
    )
    (net (code "126") (name "/SYS-RESETn") (class "Default")
      (node (ref "U4") (pin "2") (pinfunction "RESETn_2") (pintype "output"))
    )
    (net (code "127") (name "/SYS-SHDNn") (class "Default")
      (node (ref "U1") (pin "F3") (pinfunction "nSHDN_F3") (pintype "output"))
    )
    (net (code "128") (name "/SYS-WKUP") (class "Default")
      (node (ref "R19") (pin "1") (pinfunction "1_1") (pintype "passive"))
      (node (ref "U1") (pin "C3") (pinfunction "WKUP_C3") (pintype "input"))
    )
    (net (code "129") (name "/UOTG-DM") (class "Default")
      (node (ref "R18") (pin "1") (pinfunction "1_1") (pintype "passive"))
      (node (ref "U1") (pin "U16") (pinfunction "HHSDMB/DHSDM_U16") (pintype "bidirectional"))
    )
    (net (code "130") (name "/UOTG-DP") (class "Default")
      (node (ref "R15") (pin "1") (pinfunction "1_1") (pintype "passive"))
      (node (ref "U1") (pin "U15") (pinfunction "HHSDPB/DHSDP_U15") (pintype "bidirectional"))
    )
    (net (code "131") (name "/USBH-DM") (class "Default")
      (node (ref "R14") (pin "1") (pinfunction "1_1") (pintype "passive"))
      (node (ref "U1") (pin "R17") (pinfunction "HHSDMA_R17") (pintype "bidirectional"))
    )
    (net (code "132") (name "/USBH-DP") (class "Default")
      (node (ref "R13") (pin "1") (pinfunction "1_1") (pintype "passive"))
      (node (ref "U1") (pin "T17") (pinfunction "HHSDPA_T17") (pintype "bidirectional"))
    )
    (net (code "133") (name "Net-(LD1-Pad1)") (class "Default")
      (node (ref "LD1") (pin "1") (pinfunction "1_1") (pintype "passive"))
      (node (ref "RN8") (pin "7") (pinfunction "7_7") (pintype "passive"))
    )
    (net (code "134") (name "Net-(LD2-Pad1)") (class "Default")
      (node (ref "LD2") (pin "1") (pinfunction "1_1") (pintype "passive"))
      (node (ref "RN8") (pin "5") (pinfunction "5_5") (pintype "passive"))
    )
    (net (code "135") (name "Net-(LD3-Pad1)") (class "Default")
      (node (ref "LD3") (pin "1") (pinfunction "1_1") (pintype "passive"))
      (node (ref "RN8") (pin "3") (pinfunction "3_3") (pintype "passive"))
    )
    (net (code "136") (name "Net-(LD4-Pad1)") (class "Default")
      (node (ref "LD4") (pin "1") (pinfunction "1_1") (pintype "passive"))
      (node (ref "RN8") (pin "1") (pinfunction "1_1") (pintype "passive"))
    )
    (net (code "137") (name "Net-(U1C-HFSDMA)") (class "Default")
      (node (ref "R14") (pin "2") (pinfunction "2_2") (pintype "passive"))
      (node (ref "U1") (pin "R18") (pinfunction "HFSDMA_R18") (pintype "bidirectional"))
    )
    (net (code "138") (name "Net-(U1C-HFSDMB{slash}DFSDM)") (class "Default")
      (node (ref "R18") (pin "2") (pinfunction "2_2") (pintype "passive"))
      (node (ref "U1") (pin "V16") (pinfunction "HFSDMB/DFSDM_V16") (pintype "bidirectional"))
    )
    (net (code "139") (name "Net-(U1C-HFSDPA)") (class "Default")
      (node (ref "R13") (pin "2") (pinfunction "2_2") (pintype "passive"))
      (node (ref "U1") (pin "T18") (pinfunction "HFSDPA_T18") (pintype "bidirectional"))
    )
    (net (code "140") (name "Net-(U1C-HFSDPB{slash}DFSDP)") (class "Default")
      (node (ref "R15") (pin "2") (pinfunction "2_2") (pintype "passive"))
      (node (ref "U1") (pin "V15") (pinfunction "HFSDPB/DFSDP_V15") (pintype "bidirectional"))
    )
    (net (code "141") (name "Net-(U1C-VBG)") (class "Default")
      (node (ref "C33") (pin "1") (pinfunction "1_1") (pintype "passive"))
      (node (ref "R17") (pin "1") (pinfunction "1_1") (pintype "passive"))
      (node (ref "U1") (pin "V18") (pinfunction "VBG_V18") (pintype "passive"))
    )
    (net (code "142") (name "Net-(U1C-XIN)") (class "Default")
      (node (ref "C27") (pin "2") (pinfunction "2_2") (pintype "passive"))
      (node (ref "U1") (pin "V12") (pinfunction "XIN_V12") (pintype "input"))
      (node (ref "X1") (pin "1") (pinfunction "1_1") (pintype "passive"))
    )
    (net (code "143") (name "Net-(U1C-XIN32)") (class "Default")
      (node (ref "C30") (pin "2") (pinfunction "2_2") (pintype "passive"))
      (node (ref "R16") (pin "2") (pinfunction "2_2") (pintype "passive"))
      (node (ref "U1") (pin "C1") (pinfunction "XIN32_C1") (pintype "input"))
      (node (ref "X2") (pin "2") (pinfunction "2_2") (pintype "passive"))
    )
    (net (code "144") (name "Net-(U1C-XOUT)") (class "Default")
      (node (ref "C29") (pin "2") (pinfunction "2_2") (pintype "passive"))
      (node (ref "U1") (pin "V11") (pinfunction "XOUT_V11") (pintype "output"))
      (node (ref "X1") (pin "3") (pinfunction "3_3") (pintype "passive"))
    )
    (net (code "145") (name "Net-(U1C-XOUT32)") (class "Default")
      (node (ref "C32") (pin "2") (pinfunction "2_2") (pintype "passive"))
      (node (ref "R16") (pin "1") (pinfunction "1_1") (pintype "passive"))
      (node (ref "U1") (pin "D1") (pinfunction "XOUT32_D1") (pintype "output"))
      (node (ref "X2") (pin "1") (pinfunction "1_1") (pintype "passive"))
    )
    (net (code "146") (name "VDD1V0") (class "Default")
      (node (ref "C35") (pin "2") (pinfunction "2_2") (pintype "passive"))
      (node (ref "C50") (pin "2") (pinfunction "2_2") (pintype "passive"))
      (node (ref "C51") (pin "2") (pinfunction "2_2") (pintype "passive"))
      (node (ref "C52") (pin "2") (pinfunction "2_2") (pintype "passive"))
      (node (ref "C53") (pin "2") (pinfunction "2_2") (pintype "passive"))
      (node (ref "C54") (pin "2") (pinfunction "2_2") (pintype "passive"))
      (node (ref "F2") (pin "1") (pinfunction "1_1") (pintype "passive"))
      (node (ref "F3") (pin "1") (pinfunction "1_1") (pintype "passive"))
      (node (ref "U1") (pin "E18") (pinfunction "VDDCORE_E18") (pintype "passive"))
      (node (ref "U1") (pin "G12") (pinfunction "VDDCORE_G12") (pintype "passive"))
      (node (ref "U1") (pin "G13") (pinfunction "VDDCORE_G13") (pintype "passive"))
      (node (ref "U1") (pin "H11") (pinfunction "VDDCORE_H11") (pintype "passive"))
      (node (ref "U1") (pin "U18") (pinfunction "VDDUTMIC_U18") (pintype "passive"))
    )
    (net (code "147") (name "VDD1V0PLL") (class "Default")
      (node (ref "C34") (pin "2") (pinfunction "2_2") (pintype "passive"))
      (node (ref "F3") (pin "2") (pinfunction "2_2") (pintype "passive"))
      (node (ref "U1") (pin "P11") (pinfunction "VDDPLLA_P11") (pintype "passive"))
    )
    (net (code "148") (name "VDD1V0UPLL") (class "Default")
      (node (ref "C31") (pin "2") (pinfunction "2_2") (pintype "passive"))
      (node (ref "F2") (pin "2") (pinfunction "2_2") (pintype "passive"))
      (node (ref "U1") (pin "V13") (pinfunction "VDDPLLUTMI_V13") (pintype "passive"))
    )
    (net (code "149") (name "VDD1V8") (class "Default")
      (node (ref "C36") (pin "2") (pinfunction "2_2") (pintype "passive"))
      (node (ref "C37") (pin "2") (pinfunction "2_2") (pintype "passive"))
      (node (ref "C38") (pin "2") (pinfunction "2_2") (pintype "passive"))
      (node (ref "C39") (pin "2") (pinfunction "2_2") (pintype "passive"))
      (node (ref "U1") (pin "H3") (pinfunction "VDDIOP1_H3") (pintype "passive"))
      (node (ref "U1") (pin "K13") (pinfunction "VDDIOM0_K13") (pintype "passive"))
      (node (ref "U1") (pin "L12") (pinfunction "VDDIOM0_L12") (pintype "passive"))
      (node (ref "U1") (pin "L13") (pinfunction "VDDIOM0_L13") (pintype "passive"))
      (node (ref "U1") (pin "M14") (pinfunction "VDDIOM0_M14") (pintype "passive"))
    )
    (net (code "150") (name "VDD3V3") (class "Default")
      (node (ref "C40") (pin "2") (pinfunction "2_2") (pintype "passive"))
      (node (ref "C41") (pin "2") (pinfunction "2_2") (pintype "passive"))
      (node (ref "C42") (pin "2") (pinfunction "2_2") (pintype "passive"))
      (node (ref "C43") (pin "2") (pinfunction "2_2") (pintype "passive"))
      (node (ref "C44") (pin "2") (pinfunction "2_2") (pintype "passive"))
      (node (ref "C45") (pin "2") (pinfunction "2_2") (pintype "passive"))
      (node (ref "C46") (pin "2") (pinfunction "2_2") (pintype "passive"))
      (node (ref "C47") (pin "2") (pinfunction "2_2") (pintype "passive"))
      (node (ref "C48") (pin "2") (pinfunction "2_2") (pintype "passive"))
      (node (ref "C49") (pin "2") (pinfunction "2_2") (pintype "passive"))
      (node (ref "C55") (pin "2") (pinfunction "2_2") (pintype "passive"))
      (node (ref "C56") (pin "2") (pinfunction "2_2") (pintype "passive"))
      (node (ref "F1") (pin "1") (pinfunction "1_1") (pintype "passive"))
      (node (ref "LD1") (pin "2") (pinfunction "2_2") (pintype "passive"))
      (node (ref "LD2") (pin "2") (pinfunction "2_2") (pintype "passive"))
      (node (ref "LD3") (pin "2") (pinfunction "2_2") (pintype "passive"))
      (node (ref "LD4") (pin "2") (pinfunction "2_2") (pintype "passive"))
      (node (ref "R20") (pin "2") (pinfunction "2_2") (pintype "passive"))
      (node (ref "R22") (pin "2") (pinfunction "2_2") (pintype "passive"))
      (node (ref "R23") (pin "2") (pinfunction "2_2") (pintype "passive"))
      (node (ref "R24") (pin "2") (pinfunction "2_2") (pintype "passive"))
      (node (ref "R25") (pin "2") (pinfunction "2_2") (pintype "passive"))
      (node (ref "R26") (pin "2") (pinfunction "2_2") (pintype "passive"))
      (node (ref "U1") (pin "D16") (pinfunction "VDDIOM1_D16") (pintype "passive"))
      (node (ref "U1") (pin "E2") (pinfunction "TSADVREF_E2") (pintype "passive"))
      (node (ref "U1") (pin "E3") (pinfunction "VDDANA_E3") (pintype "passive"))
      (node (ref "U1") (pin "F6") (pinfunction "VDDIOM1_F6") (pintype "passive"))
      (node (ref "U1") (pin "G10") (pinfunction "VDDIOM1_G10") (pintype "passive"))
      (node (ref "U1") (pin "G11") (pinfunction "VDDIOM1_G11") (pintype "passive"))
      (node (ref "U1") (pin "K10") (pinfunction "VDDIOP0_K10") (pintype "passive"))
      (node (ref "U1") (pin "K9") (pinfunction "VDDIOP0_K9") (pintype "passive"))
      (node (ref "U1") (pin "T11") (pinfunction "BMS_T11") (pintype "input"))
      (node (ref "U1") (pin "V14") (pinfunction "VDDIOP2_V14") (pintype "passive"))
      (node (ref "U1") (pin "V17") (pinfunction "VDDUTMII_V17") (pintype "passive"))
      (node (ref "U4") (pin "4") (pinfunction "VCC_4") (pintype "passive"))
      (node (ref "U5") (pin "8") (pinfunction "VCC_8") (pintype "power_in"))
    )
    (net (code "151") (name "VDD3V3OSC") (class "Default")
      (node (ref "C28") (pin "2") (pinfunction "2_2") (pintype "passive"))
      (node (ref "F1") (pin "2") (pinfunction "2_2") (pintype "passive"))
      (node (ref "U1") (pin "U11") (pinfunction "VDDOSC_U11") (pintype "passive"))
    )
    (net (code "152") (name "VDDBU") (class "Default")
      (node (ref "R19") (pin "2") (pinfunction "2_2") (pintype "passive"))
      (node (ref "U1") (pin "D4") (pinfunction "VDDBU_D4") (pintype "passive"))
    )
    (net (code "153") (name "VSS") (class "Default")
      (node (ref "C27") (pin "1") (pinfunction "1_1") (pintype "passive"))
      (node (ref "C28") (pin "1") (pinfunction "1_1") (pintype "passive"))
      (node (ref "C29") (pin "1") (pinfunction "1_1") (pintype "passive"))
      (node (ref "C30") (pin "1") (pinfunction "1_1") (pintype "passive"))
      (node (ref "C31") (pin "1") (pinfunction "1_1") (pintype "passive"))
      (node (ref "C32") (pin "1") (pinfunction "1_1") (pintype "passive"))
      (node (ref "C33") (pin "2") (pinfunction "2_2") (pintype "passive"))
      (node (ref "C34") (pin "1") (pinfunction "1_1") (pintype "passive"))
      (node (ref "C35") (pin "1") (pinfunction "1_1") (pintype "passive"))
      (node (ref "C36") (pin "1") (pinfunction "1_1") (pintype "passive"))
      (node (ref "C37") (pin "1") (pinfunction "1_1") (pintype "passive"))
      (node (ref "C38") (pin "1") (pinfunction "1_1") (pintype "passive"))
      (node (ref "C39") (pin "1") (pinfunction "1_1") (pintype "passive"))
      (node (ref "C40") (pin "1") (pinfunction "1_1") (pintype "passive"))
      (node (ref "C41") (pin "1") (pinfunction "1_1") (pintype "passive"))
      (node (ref "C42") (pin "1") (pinfunction "1_1") (pintype "passive"))
      (node (ref "C43") (pin "1") (pinfunction "1_1") (pintype "passive"))
      (node (ref "C44") (pin "1") (pinfunction "1_1") (pintype "passive"))
      (node (ref "C45") (pin "1") (pinfunction "1_1") (pintype "passive"))
      (node (ref "C46") (pin "1") (pinfunction "1_1") (pintype "passive"))
      (node (ref "C47") (pin "1") (pinfunction "1_1") (pintype "passive"))
      (node (ref "C48") (pin "1") (pinfunction "1_1") (pintype "passive"))
      (node (ref "C49") (pin "1") (pinfunction "1_1") (pintype "passive"))
      (node (ref "C50") (pin "1") (pinfunction "1_1") (pintype "passive"))
      (node (ref "C51") (pin "1") (pinfunction "1_1") (pintype "passive"))
      (node (ref "C52") (pin "1") (pinfunction "1_1") (pintype "passive"))
      (node (ref "C53") (pin "1") (pinfunction "1_1") (pintype "passive"))
      (node (ref "C54") (pin "1") (pinfunction "1_1") (pintype "passive"))
      (node (ref "C55") (pin "1") (pinfunction "1_1") (pintype "passive"))
      (node (ref "C56") (pin "1") (pinfunction "1_1") (pintype "passive"))
      (node (ref "R17") (pin "2") (pinfunction "2_2") (pintype "passive"))
      (node (ref "R21") (pin "2") (pinfunction "2_2") (pintype "passive"))
      (node (ref "U1") (pin "C16") (pinfunction "GNDIOM_C16") (pintype "passive"))
      (node (ref "U1") (pin "C2") (pinfunction "GNDANA_C2") (pintype "passive"))
      (node (ref "U1") (pin "D3") (pinfunction "GNDBU_D3") (pintype "passive"))
      (node (ref "U1") (pin "E4") (pinfunction "JTAGSEL_E4") (pintype "input"))
      (node (ref "U1") (pin "E5") (pinfunction "GND/TST_E5") (pintype "input"))
      (node (ref "U1") (pin "G9") (pinfunction "GNDCORE_G9") (pintype "passive"))
      (node (ref "U1") (pin "H10") (pinfunction "GNDIOP_H10") (pintype "passive"))
      (node (ref "U1") (pin "H12") (pinfunction "GNDIOM_H12") (pintype "passive"))
      (node (ref "U1") (pin "H13") (pinfunction "GNDIOM_H13") (pintype "passive"))
      (node (ref "U1") (pin "H9") (pinfunction "GNDCORE_H9") (pintype "passive"))
      (node (ref "U1") (pin "J10") (pinfunction "GNDCORE_J10") (pintype "passive"))
      (node (ref "U1") (pin "J11") (pinfunction "GNDIOP_J11") (pintype "passive"))
      (node (ref "U1") (pin "J12") (pinfunction "GNDIOM_J12") (pintype "passive"))
      (node (ref "U1") (pin "J13") (pinfunction "GNDIOM_J13") (pintype "passive"))
      (node (ref "U1") (pin "J9") (pinfunction "GNDCORE_J9") (pintype "passive"))
      (node (ref "U1") (pin "K11") (pinfunction "GNDIOM_K11") (pintype "passive"))
      (node (ref "U1") (pin "K12") (pinfunction "GNDIOM_K12") (pintype "passive"))
      (node (ref "U1") (pin "U12") (pinfunction "GNDOSC_U12") (pintype "passive"))
      (node (ref "U1") (pin "U17") (pinfunction "GNDUTMI_U17") (pintype "passive"))
      (node (ref "U4") (pin "1") (pinfunction "GND_1") (pintype "passive"))
      (node (ref "U5") (pin "1") (pinfunction "A0_1") (pintype "input"))
      (node (ref "U5") (pin "2") (pinfunction "A1_2") (pintype "input"))
      (node (ref "U5") (pin "3") (pinfunction "A2_3") (pintype "input"))
      (node (ref "U5") (pin "4") (pinfunction "VSS_4") (pintype "power_in"))
      (node (ref "U5") (pin "7") (pinfunction "WP_7") (pintype "input"))
      (node (ref "X1") (pin "2") (pinfunction "2_2") (pintype "passive"))
      (node (ref "X1") (pin "4") (pinfunction "4_4") (pintype "passive"))
    )
    (net (code "154") (name "unconnected-(U1B-PA6-PadM3)") (class "Default")
      (node (ref "U1") (pin "M3") (pinfunction "PA6_M3") (pintype "bidirectional+no_connect"))
    )
    (net (code "155") (name "unconnected-(U1B-PA7-PadM4)") (class "Default")
      (node (ref "U1") (pin "M4") (pinfunction "PA7_M4") (pintype "bidirectional+no_connect"))
    )
    (net (code "156") (name "unconnected-(U1B-PA9-PadN2)") (class "Default")
      (node (ref "U1") (pin "N2") (pinfunction "PA9_N2") (pintype "bidirectional+no_connect"))
    )
    (net (code "157") (name "unconnected-(U1B-PB1{slash}SPI0_MOSI-PadV2)") (class "Default")
      (node (ref "U1") (pin "V2") (pinfunction "PB1/SPI0_MOSI_V2") (pintype "bidirectional+no_connect"))
    )
    (net (code "158") (name "unconnected-(U1B-PB2{slash}SPI0_SPCK-PadV3)") (class "Default")
      (node (ref "U1") (pin "V3") (pinfunction "PB2/SPI0_SPCK_V3") (pintype "bidirectional+no_connect"))
    )
    (net (code "159") (name "unconnected-(U1B-PB3{slash}SPI0_NPCS0-PadU4)") (class "Default")
      (node (ref "U1") (pin "U4") (pinfunction "PB3/SPI0_NPCS0_U4") (pintype "bidirectional+no_connect"))
    )
    (net (code "160") (name "unconnected-(U1B-PD28{slash}SPI1_NPCS1-PadP9)") (class "Default")
      (node (ref "U1") (pin "P9") (pinfunction "PD28/SPI1_NPCS1_P9") (pintype "bidirectional+no_connect"))
    )
  )
)
